# Isolators_HV.net
KiCad netlist of a schematic drawn in Altium Designer
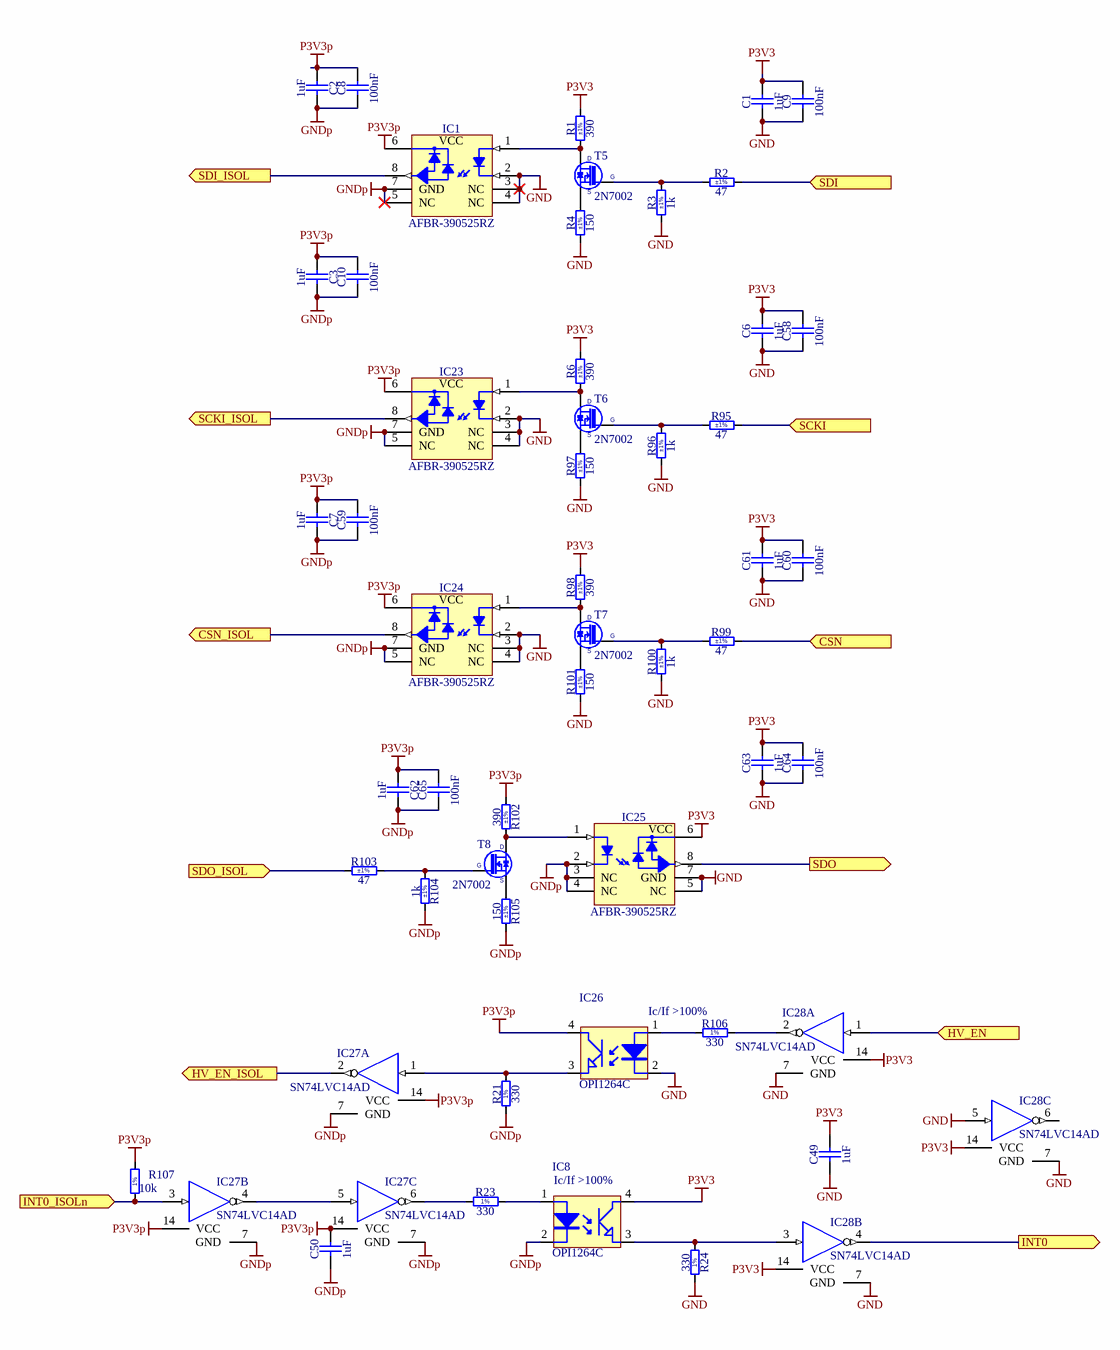
[diagram p0: Isolators_HV.SchDoc]

(export (version "E")
  (design (tool "Eeschema 10.0.6"))
  (components
    (comp (ref "C1")
      (value "1uF")
      (footprint "CAPC1005X55N")
      (description "Non-polarised capacitor")
      (fields
        (field (name "PART NUMBER") "CC0402_1UF_16V_10%_X5R")
        (field (name "VOLTAGE") "16V")
        (field (name "AUTHOR") "CERN DEM JLC")
      )
      (libsource (lib "Capacitors") (part "Capacitor - non polarized"))
    )
    (comp (ref "C2")
      (value "1uF")
      (footprint "CAPC1005X55N")
      (description "Non-polarised capacitor")
      (fields
        (field (name "PART NUMBER") "CC0402_1UF_16V_10%_X5R")
        (field (name "VOLTAGE") "16V")
        (field (name "AUTHOR") "CERN DEM JLC")
      )
      (libsource (lib "Capacitors") (part "Capacitor - non polarized"))
    )
    (comp (ref "C3")
      (value "1uF")
      (footprint "CAPC1005X55N")
      (description "Non-polarised capacitor")
      (fields
        (field (name "PART NUMBER") "CC0402_1UF_16V_10%_X5R")
        (field (name "VOLTAGE") "16V")
        (field (name "AUTHOR") "CERN DEM JLC")
      )
      (libsource (lib "Capacitors") (part "Capacitor - non polarized"))
    )
    (comp (ref "C6")
      (value "1uF")
      (footprint "CAPC1005X55N")
      (description "Non-polarised capacitor")
      (fields
        (field (name "PART NUMBER") "CC0402_1UF_16V_10%_X5R")
        (field (name "VOLTAGE") "16V")
        (field (name "AUTHOR") "CERN DEM JLC")
      )
      (libsource (lib "Capacitors") (part "Capacitor - non polarized"))
    )
    (comp (ref "C7")
      (value "1uF")
      (footprint "CAPC1005X55N")
      (description "Non-polarised capacitor")
      (fields
        (field (name "PART NUMBER") "CC0402_1UF_16V_10%_X5R")
        (field (name "VOLTAGE") "16V")
        (field (name "AUTHOR") "CERN DEM JLC")
      )
      (libsource (lib "Capacitors") (part "Capacitor - non polarized"))
    )
    (comp (ref "C8")
      (value "100nF")
      (footprint "CAPC1005X55N")
      (description "Non-polarised capacitor")
      (fields
        (field (name "PART NUMBER") "CC0402_100NF_16V_10%_X5R")
        (field (name "VOLTAGE") "16V")
        (field (name "AUTHOR") "CERN DEM JLC")
      )
      (libsource (lib "Capacitors") (part "Capacitor - non polarized"))
    )
    (comp (ref "C9")
      (value "100nF")
      (footprint "CAPC1005X55N")
      (description "Non-polarised capacitor")
      (fields
        (field (name "PART NUMBER") "CC0402_100NF_16V_10%_X5R")
        (field (name "VOLTAGE") "16V")
        (field (name "AUTHOR") "CERN DEM JLC")
      )
      (libsource (lib "Capacitors") (part "Capacitor - non polarized"))
    )
    (comp (ref "C10")
      (value "100nF")
      (footprint "CAPC1005X55N")
      (description "Non-polarised capacitor")
      (fields
        (field (name "PART NUMBER") "CC0402_100NF_16V_10%_X5R")
        (field (name "VOLTAGE") "16V")
        (field (name "AUTHOR") "CERN DEM JLC")
      )
      (libsource (lib "Capacitors") (part "Capacitor - non polarized"))
    )
    (comp (ref "C49")
      (value "1uF")
      (footprint "CAPC1005X55N")
      (description "Non-polarised capacitor")
      (fields
        (field (name "PART NUMBER") "CC0402_1UF_16V_10%_X5R")
        (field (name "VOLTAGE") "16V")
        (field (name "AUTHOR") "CERN DEM JLC")
      )
      (libsource (lib "Capacitors") (part "Capacitor - non polarized"))
    )
    (comp (ref "C50")
      (value "1uF")
      (footprint "CAPC1005X55N")
      (description "Non-polarised capacitor")
      (fields
        (field (name "PART NUMBER") "CC0402_1UF_16V_10%_X5R")
        (field (name "VOLTAGE") "16V")
        (field (name "AUTHOR") "CERN DEM JLC")
      )
      (libsource (lib "Capacitors") (part "Capacitor - non polarized"))
    )
    (comp (ref "C58")
      (value "100nF")
      (footprint "CAPC1005X55N")
      (description "Non-polarised capacitor")
      (fields
        (field (name "PART NUMBER") "CC0402_100NF_16V_10%_X5R")
        (field (name "VOLTAGE") "16V")
        (field (name "AUTHOR") "CERN DEM JLC")
      )
      (libsource (lib "Capacitors") (part "Capacitor - non polarized"))
    )
    (comp (ref "C59")
      (value "100nF")
      (footprint "CAPC1005X55N")
      (description "Non-polarised capacitor")
      (fields
        (field (name "PART NUMBER") "CC0402_100NF_16V_10%_X5R")
        (field (name "VOLTAGE") "16V")
        (field (name "AUTHOR") "CERN DEM JLC")
      )
      (libsource (lib "Capacitors") (part "Capacitor - non polarized"))
    )
    (comp (ref "C60")
      (value "100nF")
      (footprint "CAPC1005X55N")
      (description "Non-polarised capacitor")
      (fields
        (field (name "PART NUMBER") "CC0402_100NF_16V_10%_X5R")
        (field (name "VOLTAGE") "16V")
        (field (name "AUTHOR") "CERN DEM JLC")
      )
      (libsource (lib "Capacitors") (part "Capacitor - non polarized"))
    )
    (comp (ref "C61")
      (value "1uF")
      (footprint "CAPC1005X55N")
      (description "Non-polarised capacitor")
      (fields
        (field (name "PART NUMBER") "CC0402_1UF_16V_10%_X5R")
        (field (name "VOLTAGE") "16V")
        (field (name "AUTHOR") "CERN DEM JLC")
      )
      (libsource (lib "Capacitors") (part "Capacitor - non polarized"))
    )
    (comp (ref "C62")
      (value "1uF")
      (footprint "CAPC1005X55N")
      (description "Non-polarised capacitor")
      (fields
        (field (name "PART NUMBER") "CC0402_1UF_16V_10%_X5R")
        (field (name "VOLTAGE") "16V")
        (field (name "AUTHOR") "CERN DEM JLC")
      )
      (libsource (lib "Capacitors") (part "Capacitor - non polarized"))
    )
    (comp (ref "C63")
      (value "1uF")
      (footprint "CAPC1005X55N")
      (description "Non-polarised capacitor")
      (fields
        (field (name "PART NUMBER") "CC0402_1UF_16V_10%_X5R")
        (field (name "VOLTAGE") "16V")
        (field (name "AUTHOR") "CERN DEM JLC")
      )
      (libsource (lib "Capacitors") (part "Capacitor - non polarized"))
    )
    (comp (ref "C64")
      (value "100nF")
      (footprint "CAPC1005X55N")
      (description "Non-polarised capacitor")
      (fields
        (field (name "PART NUMBER") "CC0402_100NF_16V_10%_X5R")
        (field (name "VOLTAGE") "16V")
        (field (name "AUTHOR") "CERN DEM JLC")
      )
      (libsource (lib "Capacitors") (part "Capacitor - non polarized"))
    )
    (comp (ref "C65")
      (value "100nF")
      (footprint "CAPC1005X55N")
      (description "Non-polarised capacitor")
      (fields
        (field (name "PART NUMBER") "CC0402_100NF_16V_10%_X5R")
        (field (name "VOLTAGE") "16V")
        (field (name "AUTHOR") "CERN DEM JLC")
      )
      (libsource (lib "Capacitors") (part "Capacitor - non polarized"))
    )
    (comp (ref "IC1")
      (value "AFBR-390525RZ")
      (footprint "BROADCOM_AFBR-390525RZ")
      (description "High Voltage Galvanic Insulation Link for DC to 5MBaud")
      (fields (field (name "MANUFACTURER") "BROADCOM") (field (name "AUTHOR") "CERN DEM HF"))
      (libsource (lib "ICs And Semiconductors") (part "AFBR-3905XXRZ"))
    )
    (comp (ref "IC8")
      (value "OPI1264C")
      (footprint "OPI1264C")
      (description "10kV opto-coupler")
      (libsource (lib "LIBRARY_SCH") (part "OPTO-OPI1264C"))
    )
    (comp (ref "IC23")
      (value "AFBR-390525RZ")
      (footprint "BROADCOM_AFBR-390525RZ")
      (description "High Voltage Galvanic Insulation Link for DC to 5MBaud")
      (fields (field (name "MANUFACTURER") "BROADCOM") (field (name "AUTHOR") "CERN DEM HF"))
      (libsource (lib "ICs And Semiconductors") (part "AFBR-3905XXRZ"))
    )
    (comp (ref "IC24")
      (value "AFBR-390525RZ")
      (footprint "BROADCOM_AFBR-390525RZ")
      (description "High Voltage Galvanic Insulation Link for DC to 5MBaud")
      (fields (field (name "MANUFACTURER") "BROADCOM") (field (name "AUTHOR") "CERN DEM HF"))
      (libsource (lib "ICs And Semiconductors") (part "AFBR-3905XXRZ"))
    )
    (comp (ref "IC25")
      (value "AFBR-390525RZ")
      (footprint "BROADCOM_AFBR-390525RZ")
      (description "High Voltage Galvanic Insulation Link for DC to 5MBaud")
      (fields (field (name "MANUFACTURER") "BROADCOM") (field (name "AUTHOR") "CERN DEM HF"))
      (libsource (lib "") (part "AFBR-3905XXRZ_1"))
    )
    (comp (ref "IC26")
      (value "OPI1264C")
      (footprint "OPI1264C")
      (description "10kV opto-coupler")
      (libsource (lib "") (part "OPTO-OPI1264C_1"))
    )
    (comp (ref "IC27")
      (value "SN74LVC14AD")
      (footprint "SOIC127P600X175-14N")
      (description "Hex Schmitt-Trigger Inverter")
      (fields (field (name "MANUFACTURER") "TEXAS INSTRUMENTS") (field (name "AUTHOR") "CERN DEM JMW"))
      (libsource (lib "ICs And Semiconductors") (part "7414"))
    )
    (comp (ref "IC28")
      (value "SN74LVC14AD")
      (footprint "SOIC127P600X175-14N")
      (description "Hex Schmitt-Trigger Inverter")
      (fields (field (name "MANUFACTURER") "TEXAS INSTRUMENTS") (field (name "AUTHOR") "CERN DEM JMW"))
      (libsource (lib "ICs And Semiconductors") (part "7414"))
    )
    (comp (ref "R1")
      (value "390")
      (footprint "RESC1608X55N")
      (description "Resistor - 1%")
      (fields
        (field (name "TOLERANCE") "±1%")
        (field (name "PART NUMBER") "R0603_390R_1%_0.1W_100PPM")
        (field (name "POWER") "0.1W")
        (field (name "AUTHOR") "CERN DEM JLC")
      )
      (libsource (lib "Resistors") (part "Resistor - 1%"))
    )
    (comp (ref "R2")
      (value "47")
      (footprint "RESC1005X40N")
      (description "Resistor - 1%")
      (fields
        (field (name "TOLERANCE") "±1%")
        (field (name "PART NUMBER") "R0402_47R_1%_0.0625W_100PPM")
        (field (name "POWER") "0.0625W")
        (field (name "AUTHOR") "CERN DEM JLC")
      )
      (libsource (lib "Resistors") (part "Resistor - 1%"))
    )
    (comp (ref "R3")
      (value "1k")
      (footprint "RESC1005X40N")
      (description "Resistor - 1%")
      (fields
        (field (name "TOLERANCE") "±1%")
        (field (name "PART NUMBER") "R0402_1K_1%_0.0625W_100PPM")
        (field (name "POWER") "0.0625W")
        (field (name "AUTHOR") "CERN DEM JLC")
      )
      (libsource (lib "Resistors") (part "Resistor - 1%"))
    )
    (comp (ref "R4")
      (value "150")
      (footprint "RESC1608X55N")
      (description "Resistor - 1%")
      (fields
        (field (name "TOLERANCE") "±1%")
        (field (name "PART NUMBER") "R0603_150R_1%_0.1W_100PPM")
        (field (name "POWER") "0.1W")
        (field (name "AUTHOR") "CERN DEM JLC")
      )
      (libsource (lib "Resistors") (part "Resistor - 1%"))
    )
    (comp (ref "R6")
      (value "390")
      (footprint "RESC1608X55N")
      (description "Resistor - 1%")
      (fields
        (field (name "TOLERANCE") "±1%")
        (field (name "PART NUMBER") "R0603_390R_1%_0.1W_100PPM")
        (field (name "POWER") "0.1W")
        (field (name "AUTHOR") "CERN DEM JLC")
      )
      (libsource (lib "Resistors") (part "Resistor - 1%"))
    )
    (comp (ref "R21")
      (value "330")
      (footprint "RESC1005X40N")
      (description "Resistor - 1%")
      (fields
        (field (name "PART NUMBER") "R0402_330R_1%_0.0625W_100PPM")
        (field (name "POWER") "0.0625W")
        (field (name "AUTHOR") "CERN DEM JLC")
      )
      (libsource (lib "") (part "Resistor - 1%_1"))
    )
    (comp (ref "R23")
      (value "330")
      (footprint "RESC1005X40N")
      (description "Resistor - 1%")
      (fields
        (field (name "PART NUMBER") "R0402_330R_1%_0.0625W_100PPM")
        (field (name "POWER") "0.0625W")
        (field (name "AUTHOR") "CERN DEM JLC")
      )
      (libsource (lib "") (part "Resistor - 1%_1"))
    )
    (comp (ref "R24")
      (value "330")
      (footprint "RESC1005X40N")
      (description "Resistor - 1%")
      (fields
        (field (name "PART NUMBER") "R0402_330R_1%_0.0625W_100PPM")
        (field (name "POWER") "0.0625W")
        (field (name "AUTHOR") "CERN DEM JLC")
      )
      (libsource (lib "") (part "Resistor - 1%_1"))
    )
    (comp (ref "R95")
      (value "47")
      (footprint "RESC1005X40N")
      (description "Resistor - 1%")
      (fields
        (field (name "TOLERANCE") "±1%")
        (field (name "PART NUMBER") "R0402_47R_1%_0.0625W_100PPM")
        (field (name "POWER") "0.0625W")
        (field (name "AUTHOR") "CERN DEM JLC")
      )
      (libsource (lib "Resistors") (part "Resistor - 1%"))
    )
    (comp (ref "R96")
      (value "1k")
      (footprint "RESC1005X40N")
      (description "Resistor - 1%")
      (fields
        (field (name "TOLERANCE") "±1%")
        (field (name "PART NUMBER") "R0402_1K_1%_0.0625W_100PPM")
        (field (name "POWER") "0.0625W")
        (field (name "AUTHOR") "CERN DEM JLC")
      )
      (libsource (lib "Resistors") (part "Resistor - 1%"))
    )
    (comp (ref "R97")
      (value "150")
      (footprint "RESC1608X55N")
      (description "Resistor - 1%")
      (fields
        (field (name "TOLERANCE") "±1%")
        (field (name "PART NUMBER") "R0603_150R_1%_0.1W_100PPM")
        (field (name "POWER") "0.1W")
        (field (name "AUTHOR") "CERN DEM JLC")
      )
      (libsource (lib "Resistors") (part "Resistor - 1%"))
    )
    (comp (ref "R98")
      (value "390")
      (footprint "RESC1608X55N")
      (description "Resistor - 1%")
      (fields
        (field (name "TOLERANCE") "±1%")
        (field (name "PART NUMBER") "R0603_390R_1%_0.1W_100PPM")
        (field (name "POWER") "0.1W")
        (field (name "AUTHOR") "CERN DEM JLC")
      )
      (libsource (lib "Resistors") (part "Resistor - 1%"))
    )
    (comp (ref "R99")
      (value "47")
      (footprint "RESC1005X40N")
      (description "Resistor - 1%")
      (fields
        (field (name "TOLERANCE") "±1%")
        (field (name "PART NUMBER") "R0402_47R_1%_0.0625W_100PPM")
        (field (name "POWER") "0.0625W")
        (field (name "AUTHOR") "CERN DEM JLC")
      )
      (libsource (lib "Resistors") (part "Resistor - 1%"))
    )
    (comp (ref "R100")
      (value "1k")
      (footprint "RESC1005X40N")
      (description "Resistor - 1%")
      (fields
        (field (name "TOLERANCE") "±1%")
        (field (name "PART NUMBER") "R0402_1K_1%_0.0625W_100PPM")
        (field (name "POWER") "0.0625W")
        (field (name "AUTHOR") "CERN DEM JLC")
      )
      (libsource (lib "Resistors") (part "Resistor - 1%"))
    )
    (comp (ref "R101")
      (value "150")
      (footprint "RESC1608X55N")
      (description "Resistor - 1%")
      (fields
        (field (name "TOLERANCE") "±1%")
        (field (name "PART NUMBER") "R0603_150R_1%_0.1W_100PPM")
        (field (name "POWER") "0.1W")
        (field (name "AUTHOR") "CERN DEM JLC")
      )
      (libsource (lib "Resistors") (part "Resistor - 1%"))
    )
    (comp (ref "R102")
      (value "390")
      (footprint "RESC1608X55N")
      (description "Resistor - 1%")
      (fields
        (field (name "TOLERANCE") "±1%")
        (field (name "PART NUMBER") "R0603_390R_1%_0.1W_100PPM")
        (field (name "POWER") "0.1W")
        (field (name "AUTHOR") "CERN DEM JLC")
      )
      (libsource (lib "Resistors") (part "Resistor - 1%"))
    )
    (comp (ref "R103")
      (value "47")
      (footprint "RESC1005X40N")
      (description "Resistor - 1%")
      (fields
        (field (name "TOLERANCE") "±1%")
        (field (name "PART NUMBER") "R0402_47R_1%_0.0625W_100PPM")
        (field (name "POWER") "0.0625W")
        (field (name "AUTHOR") "CERN DEM JLC")
      )
      (libsource (lib "Resistors") (part "Resistor - 1%"))
    )
    (comp (ref "R104")
      (value "1k")
      (footprint "RESC1005X40N")
      (description "Resistor - 1%")
      (fields
        (field (name "TOLERANCE") "±1%")
        (field (name "PART NUMBER") "R0402_1K_1%_0.0625W_100PPM")
        (field (name "POWER") "0.0625W")
        (field (name "AUTHOR") "CERN DEM JLC")
      )
      (libsource (lib "Resistors") (part "Resistor - 1%"))
    )
    (comp (ref "R105")
      (value "150")
      (footprint "RESC1608X55N")
      (description "Resistor - 1%")
      (fields
        (field (name "TOLERANCE") "±1%")
        (field (name "PART NUMBER") "R0603_150R_1%_0.1W_100PPM")
        (field (name "POWER") "0.1W")
        (field (name "AUTHOR") "CERN DEM JLC")
      )
      (libsource (lib "Resistors") (part "Resistor - 1%"))
    )
    (comp (ref "R106")
      (value "330")
      (footprint "RESC1005X40N")
      (description "Resistor - 1%")
      (fields
        (field (name "PART NUMBER") "R0402_330R_1%_0.0625W_100PPM")
        (field (name "POWER") "0.0625W")
        (field (name "AUTHOR") "CERN DEM JLC")
      )
      (libsource (lib "") (part "Resistor - 1%_1"))
    )
    (comp (ref "R107")
      (value "10k")
      (footprint "RESC1005X40N")
      (description "Resistor - 1%")
      (fields
        (field (name "PART NUMBER") "R0402_10K_1%_0.0625W_100PPM")
        (field (name "POWER") "0.0625W")
        (field (name "AUTHOR") "CERN DEM JLC")
      )
      (libsource (lib "") (part "Resistor - 1%_1"))
    )
    (comp (ref "T5")
      (value "2N7002")
      (footprint "SOT95P240X130-3N")
      (description "N-CHANNEL MOSFET WITH DIODE")
      (fields (field (name "MANUFACTURER") "FAIRCHILD SEMICONDUCTOR") (field (name "AUTHOR") "CERN DEM JLC"))
      (libsource (lib "ICs And Semiconductors") (part "N-MOSFET-D 1G 2S 3D"))
    )
    (comp (ref "T6")
      (value "2N7002")
      (footprint "SOT95P240X130-3N")
      (description "N-CHANNEL MOSFET WITH DIODE")
      (fields (field (name "MANUFACTURER") "FAIRCHILD SEMICONDUCTOR") (field (name "AUTHOR") "CERN DEM JLC"))
      (libsource (lib "ICs And Semiconductors") (part "N-MOSFET-D 1G 2S 3D"))
    )
    (comp (ref "T7")
      (value "2N7002")
      (footprint "SOT95P240X130-3N")
      (description "N-CHANNEL MOSFET WITH DIODE")
      (fields (field (name "MANUFACTURER") "FAIRCHILD SEMICONDUCTOR") (field (name "AUTHOR") "CERN DEM JLC"))
      (libsource (lib "ICs And Semiconductors") (part "N-MOSFET-D 1G 2S 3D"))
    )
    (comp (ref "T8")
      (value "2N7002")
      (footprint "SOT95P240X130-3N")
      (description "N-CHANNEL MOSFET WITH DIODE")
      (fields (field (name "MANUFACTURER") "FAIRCHILD SEMICONDUCTOR") (field (name "AUTHOR") "CERN DEM JLC"))
      (libsource (lib "") (part "N-MOSFET-D 1G 2S 3D_1"))
    )
  )
  (nets
    (net (code "1") (name "/CSN") (class "Default")
      (node (ref "R99") (pin "2") (pinfunction "2_2") (pintype "passive"))
    )
    (net (code "2") (name "/CSN_ISOL") (class "Default")
      (node (ref "IC24") (pin "8") (pinfunction "DATA_OUT_8") (pintype "output"))
    )
    (net (code "3") (name "/HV_EN") (class "Default")
      (node (ref "IC28") (pin "1") (pinfunction "IN_1") (pintype "input"))
    )
    (net (code "4") (name "/HV_EN_ISOL") (class "Default")
      (node (ref "IC27") (pin "2") (pinfunction "OUT_2") (pintype "output"))
    )
    (net (code "5") (name "/INT0") (class "Default")
      (node (ref "IC28") (pin "4") (pinfunction "OUT_4") (pintype "output"))
    )
    (net (code "6") (name "/INT0_ISOLn") (class "Default")
      (node (ref "IC27") (pin "3") (pinfunction "IN_3") (pintype "input"))
      (node (ref "R107") (pin "1") (pinfunction "1_1") (pintype "passive"))
    )
    (net (code "7") (name "/SCKI") (class "Default")
      (node (ref "R95") (pin "2") (pinfunction "2_2") (pintype "passive"))
    )
    (net (code "8") (name "/SCKI_ISOL") (class "Default")
      (node (ref "IC23") (pin "8") (pinfunction "DATA_OUT_8") (pintype "output"))
    )
    (net (code "9") (name "/SDI") (class "Default")
      (node (ref "R2") (pin "2") (pinfunction "2_2") (pintype "passive"))
    )
    (net (code "10") (name "/SDI_ISOL") (class "Default")
      (node (ref "IC1") (pin "8") (pinfunction "DATA_OUT_8") (pintype "output"))
    )
    (net (code "11") (name "/SDO") (class "Default")
      (node (ref "IC25") (pin "8") (pinfunction "DATA_OUT_8") (pintype "output"))
    )
    (net (code "12") (name "/SDO_ISOL") (class "Default")
      (node (ref "R103") (pin "2") (pinfunction "2_2") (pintype "passive"))
    )
    (net (code "13") (name "GND") (class "Default")
      (node (ref "C1") (pin "1") (pinfunction "1_1") (pintype "passive"))
      (node (ref "C49") (pin "2") (pinfunction "2_2") (pintype "passive"))
      (node (ref "C58") (pin "1") (pinfunction "1_1") (pintype "passive"))
      (node (ref "C6") (pin "1") (pinfunction "1_1") (pintype "passive"))
      (node (ref "C60") (pin "1") (pinfunction "1_1") (pintype "passive"))
      (node (ref "C61") (pin "1") (pinfunction "1_1") (pintype "passive"))
      (node (ref "C63") (pin "2") (pinfunction "2_2") (pintype "passive"))
      (node (ref "C64") (pin "1") (pinfunction "1_1") (pintype "passive"))
      (node (ref "C9") (pin "1") (pinfunction "1_1") (pintype "passive"))
      (node (ref "IC1") (pin "2") (pinfunction "C_2") (pintype "input"))
      (node (ref "IC1") (pin "3") (pinfunction "NC_3") (pintype "open_collector"))
      (node (ref "IC1") (pin "4") (pinfunction "NC_4") (pintype "open_collector"))
      (node (ref "IC23") (pin "2") (pinfunction "C_2") (pintype "input"))
      (node (ref "IC23") (pin "3") (pinfunction "NC_3") (pintype "open_collector"))
      (node (ref "IC23") (pin "4") (pinfunction "NC_4") (pintype "open_collector"))
      (node (ref "IC24") (pin "2") (pinfunction "C_2") (pintype "input"))
      (node (ref "IC24") (pin "3") (pinfunction "NC_3") (pintype "open_collector"))
      (node (ref "IC24") (pin "4") (pinfunction "NC_4") (pintype "open_collector"))
      (node (ref "IC25") (pin "5") (pinfunction "NC_5") (pintype "open_collector"))
      (node (ref "IC25") (pin "7") (pinfunction "GND_7") (pintype "power_in"))
      (node (ref "IC26") (pin "2") (pinfunction "K_2") (pintype "passive"))
      (node (ref "IC28") (pin "5") (pinfunction "IN_5") (pintype "input"))
      (node (ref "IC28") (pin "7") (pinfunction "GND_7") (pintype "power_in"))
      (node (ref "R100") (pin "1") (pinfunction "1_1") (pintype "passive"))
      (node (ref "R101") (pin "1") (pinfunction "1_1") (pintype "passive"))
      (node (ref "R24") (pin "1") (pinfunction "1_1") (pintype "passive"))
      (node (ref "R3") (pin "1") (pinfunction "1_1") (pintype "passive"))
      (node (ref "R4") (pin "1") (pinfunction "1_1") (pintype "passive"))
      (node (ref "R96") (pin "1") (pinfunction "1_1") (pintype "passive"))
      (node (ref "R97") (pin "1") (pinfunction "1_1") (pintype "passive"))
    )
    (net (code "14") (name "GNDp") (class "Default")
      (node (ref "C10") (pin "1") (pinfunction "1_1") (pintype "passive"))
      (node (ref "C2") (pin "2") (pinfunction "2_2") (pintype "passive"))
      (node (ref "C3") (pin "2") (pinfunction "2_2") (pintype "passive"))
      (node (ref "C50") (pin "2") (pinfunction "2_2") (pintype "passive"))
      (node (ref "C59") (pin "1") (pinfunction "1_1") (pintype "passive"))
      (node (ref "C62") (pin "1") (pinfunction "1_1") (pintype "passive"))
      (node (ref "C65") (pin "1") (pinfunction "1_1") (pintype "passive"))
      (node (ref "C7") (pin "2") (pinfunction "2_2") (pintype "passive"))
      (node (ref "C8") (pin "1") (pinfunction "1_1") (pintype "passive"))
      (node (ref "IC1") (pin "5") (pinfunction "NC_5") (pintype "open_collector"))
      (node (ref "IC1") (pin "7") (pinfunction "GND_7") (pintype "power_in"))
      (node (ref "IC23") (pin "5") (pinfunction "NC_5") (pintype "open_collector"))
      (node (ref "IC23") (pin "7") (pinfunction "GND_7") (pintype "power_in"))
      (node (ref "IC24") (pin "5") (pinfunction "NC_5") (pintype "open_collector"))
      (node (ref "IC24") (pin "7") (pinfunction "GND_7") (pintype "power_in"))
      (node (ref "IC25") (pin "2") (pinfunction "C_2") (pintype "input"))
      (node (ref "IC25") (pin "3") (pinfunction "NC_3") (pintype "open_collector"))
      (node (ref "IC25") (pin "4") (pinfunction "NC_4") (pintype "open_collector"))
      (node (ref "IC27") (pin "7") (pinfunction "GND_7") (pintype "power_in"))
      (node (ref "IC8") (pin "2") (pinfunction "K_2") (pintype "passive"))
      (node (ref "R104") (pin "1") (pinfunction "1_1") (pintype "passive"))
      (node (ref "R105") (pin "1") (pinfunction "1_1") (pintype "passive"))
      (node (ref "R21") (pin "1") (pinfunction "1_1") (pintype "passive"))
    )
    (net (code "15") (name "Net-(IC1-A)") (class "Default")
      (node (ref "IC1") (pin "1") (pinfunction "A_1") (pintype "input"))
      (node (ref "R1") (pin "1") (pinfunction "1_1") (pintype "passive"))
      (node (ref "T5") (pin "3") (pinfunction "D_3") (pintype "passive"))
    )
    (net (code "16") (name "Net-(IC8-A)") (class "Default")
      (node (ref "IC8") (pin "1") (pinfunction "A_1") (pintype "passive"))
      (node (ref "R23") (pin "1") (pinfunction "1_1") (pintype "passive"))
    )
    (net (code "17") (name "Net-(IC23-A)") (class "Default")
      (node (ref "IC23") (pin "1") (pinfunction "A_1") (pintype "input"))
      (node (ref "R6") (pin "1") (pinfunction "1_1") (pintype "passive"))
      (node (ref "T6") (pin "3") (pinfunction "D_3") (pintype "passive"))
    )
    (net (code "18") (name "Net-(IC24-A)") (class "Default")
      (node (ref "IC24") (pin "1") (pinfunction "A_1") (pintype "input"))
      (node (ref "R98") (pin "1") (pinfunction "1_1") (pintype "passive"))
      (node (ref "T7") (pin "3") (pinfunction "D_3") (pintype "passive"))
    )
    (net (code "19") (name "Net-(IC25-A)") (class "Default")
      (node (ref "IC25") (pin "1") (pinfunction "A_1") (pintype "input"))
      (node (ref "R102") (pin "1") (pinfunction "1_1") (pintype "passive"))
      (node (ref "T8") (pin "3") (pinfunction "D_3") (pintype "passive"))
    )
    (net (code "20") (name "Net-(IC26-A)") (class "Default")
      (node (ref "IC26") (pin "1") (pinfunction "A_1") (pintype "passive"))
      (node (ref "R106") (pin "1") (pinfunction "1_1") (pintype "passive"))
    )
    (net (code "21") (name "Net-(IC26-E)") (class "Default")
      (node (ref "IC26") (pin "3") (pinfunction "E_3") (pintype "passive"))
      (node (ref "IC27") (pin "1") (pinfunction "IN_1") (pintype "input"))
      (node (ref "R21") (pin "2") (pinfunction "2_2") (pintype "passive"))
    )
    (net (code "22") (name "Net-(IC27B-OUT)") (class "Default")
      (node (ref "IC27") (pin "4") (pinfunction "OUT_4") (pintype "output"))
      (node (ref "IC27") (pin "5") (pinfunction "IN_5") (pintype "input"))
    )
    (net (code "23") (name "Net-(IC27C-OUT)") (class "Default")
      (node (ref "IC27") (pin "6") (pinfunction "OUT_6") (pintype "output"))
      (node (ref "R23") (pin "2") (pinfunction "2_2") (pintype "passive"))
    )
    (net (code "24") (name "Net-(IC28A-OUT)") (class "Default")
      (node (ref "IC28") (pin "2") (pinfunction "OUT_2") (pintype "output"))
      (node (ref "R106") (pin "2") (pinfunction "2_2") (pintype "passive"))
    )
    (net (code "25") (name "Net-(IC28B-IN)") (class "Default")
      (node (ref "IC28") (pin "3") (pinfunction "IN_3") (pintype "input"))
      (node (ref "IC8") (pin "3") (pinfunction "E_3") (pintype "passive"))
      (node (ref "R24") (pin "2") (pinfunction "2_2") (pintype "passive"))
    )
    (net (code "26") (name "Net-(T5-G)") (class "Default")
      (node (ref "R2") (pin "1") (pinfunction "1_1") (pintype "passive"))
      (node (ref "R3") (pin "2") (pinfunction "2_2") (pintype "passive"))
      (node (ref "T5") (pin "1") (pinfunction "G_1") (pintype "passive"))
    )
    (net (code "27") (name "Net-(T5-S)") (class "Default")
      (node (ref "R4") (pin "2") (pinfunction "2_2") (pintype "passive"))
      (node (ref "T5") (pin "2") (pinfunction "S_2") (pintype "passive"))
    )
    (net (code "28") (name "Net-(T6-G)") (class "Default")
      (node (ref "R95") (pin "1") (pinfunction "1_1") (pintype "passive"))
      (node (ref "R96") (pin "2") (pinfunction "2_2") (pintype "passive"))
      (node (ref "T6") (pin "1") (pinfunction "G_1") (pintype "passive"))
    )
    (net (code "29") (name "Net-(T6-S)") (class "Default")
      (node (ref "R97") (pin "2") (pinfunction "2_2") (pintype "passive"))
      (node (ref "T6") (pin "2") (pinfunction "S_2") (pintype "passive"))
    )
    (net (code "30") (name "Net-(T7-G)") (class "Default")
      (node (ref "R100") (pin "2") (pinfunction "2_2") (pintype "passive"))
      (node (ref "R99") (pin "1") (pinfunction "1_1") (pintype "passive"))
      (node (ref "T7") (pin "1") (pinfunction "G_1") (pintype "passive"))
    )
    (net (code "31") (name "Net-(T7-S)") (class "Default")
      (node (ref "R101") (pin "2") (pinfunction "2_2") (pintype "passive"))
      (node (ref "T7") (pin "2") (pinfunction "S_2") (pintype "passive"))
    )
    (net (code "32") (name "Net-(T8-G)") (class "Default")
      (node (ref "R103") (pin "1") (pinfunction "1_1") (pintype "passive"))
      (node (ref "R104") (pin "2") (pinfunction "2_2") (pintype "passive"))
      (node (ref "T8") (pin "1") (pinfunction "G_1") (pintype "passive"))
    )
    (net (code "33") (name "Net-(T8-S)") (class "Default")
      (node (ref "R105") (pin "2") (pinfunction "2_2") (pintype "passive"))
      (node (ref "T8") (pin "2") (pinfunction "S_2") (pintype "passive"))
    )
    (net (code "34") (name "P3V3") (class "Default")
      (node (ref "C1") (pin "2") (pinfunction "2_2") (pintype "passive"))
      (node (ref "C49") (pin "1") (pinfunction "1_1") (pintype "passive"))
      (node (ref "C58") (pin "2") (pinfunction "2_2") (pintype "passive"))
      (node (ref "C6") (pin "2") (pinfunction "2_2") (pintype "passive"))
      (node (ref "C60") (pin "2") (pinfunction "2_2") (pintype "passive"))
      (node (ref "C61") (pin "2") (pinfunction "2_2") (pintype "passive"))
      (node (ref "C63") (pin "1") (pinfunction "1_1") (pintype "passive"))
      (node (ref "C64") (pin "2") (pinfunction "2_2") (pintype "passive"))
      (node (ref "C9") (pin "2") (pinfunction "2_2") (pintype "passive"))
      (node (ref "IC25") (pin "6") (pinfunction "VCC_6") (pintype "power_in"))
      (node (ref "IC28") (pin "14") (pinfunction "VCC_14") (pintype "power_in"))
      (node (ref "IC8") (pin "4") (pinfunction "C_4") (pintype "passive"))
      (node (ref "R1") (pin "2") (pinfunction "2_2") (pintype "passive"))
      (node (ref "R6") (pin "2") (pinfunction "2_2") (pintype "passive"))
      (node (ref "R98") (pin "2") (pinfunction "2_2") (pintype "passive"))
    )
    (net (code "35") (name "P3V3p") (class "Default")
      (node (ref "C10") (pin "2") (pinfunction "2_2") (pintype "passive"))
      (node (ref "C2") (pin "1") (pinfunction "1_1") (pintype "passive"))
      (node (ref "C3") (pin "1") (pinfunction "1_1") (pintype "passive"))
      (node (ref "C50") (pin "1") (pinfunction "1_1") (pintype "passive"))
      (node (ref "C59") (pin "2") (pinfunction "2_2") (pintype "passive"))
      (node (ref "C62") (pin "2") (pinfunction "2_2") (pintype "passive"))
      (node (ref "C65") (pin "2") (pinfunction "2_2") (pintype "passive"))
      (node (ref "C7") (pin "1") (pinfunction "1_1") (pintype "passive"))
      (node (ref "C8") (pin "2") (pinfunction "2_2") (pintype "passive"))
      (node (ref "IC1") (pin "6") (pinfunction "VCC_6") (pintype "power_in"))
      (node (ref "IC23") (pin "6") (pinfunction "VCC_6") (pintype "power_in"))
      (node (ref "IC24") (pin "6") (pinfunction "VCC_6") (pintype "power_in"))
      (node (ref "IC26") (pin "4") (pinfunction "C_4") (pintype "passive"))
      (node (ref "IC27") (pin "14") (pinfunction "VCC_14") (pintype "power_in"))
      (node (ref "R102") (pin "2") (pinfunction "2_2") (pintype "passive"))
      (node (ref "R107") (pin "2") (pinfunction "2_2") (pintype "passive"))
    )
    (net (code "36") (name "unconnected-(IC28C-OUT-Pad6)") (class "Default")
      (node (ref "IC28") (pin "6") (pinfunction "OUT_6") (pintype "output"))
    )
  )
)
